# EthIO_03_Ethernet.net
KiCad netlist of a schematic drawn in Altium Designer
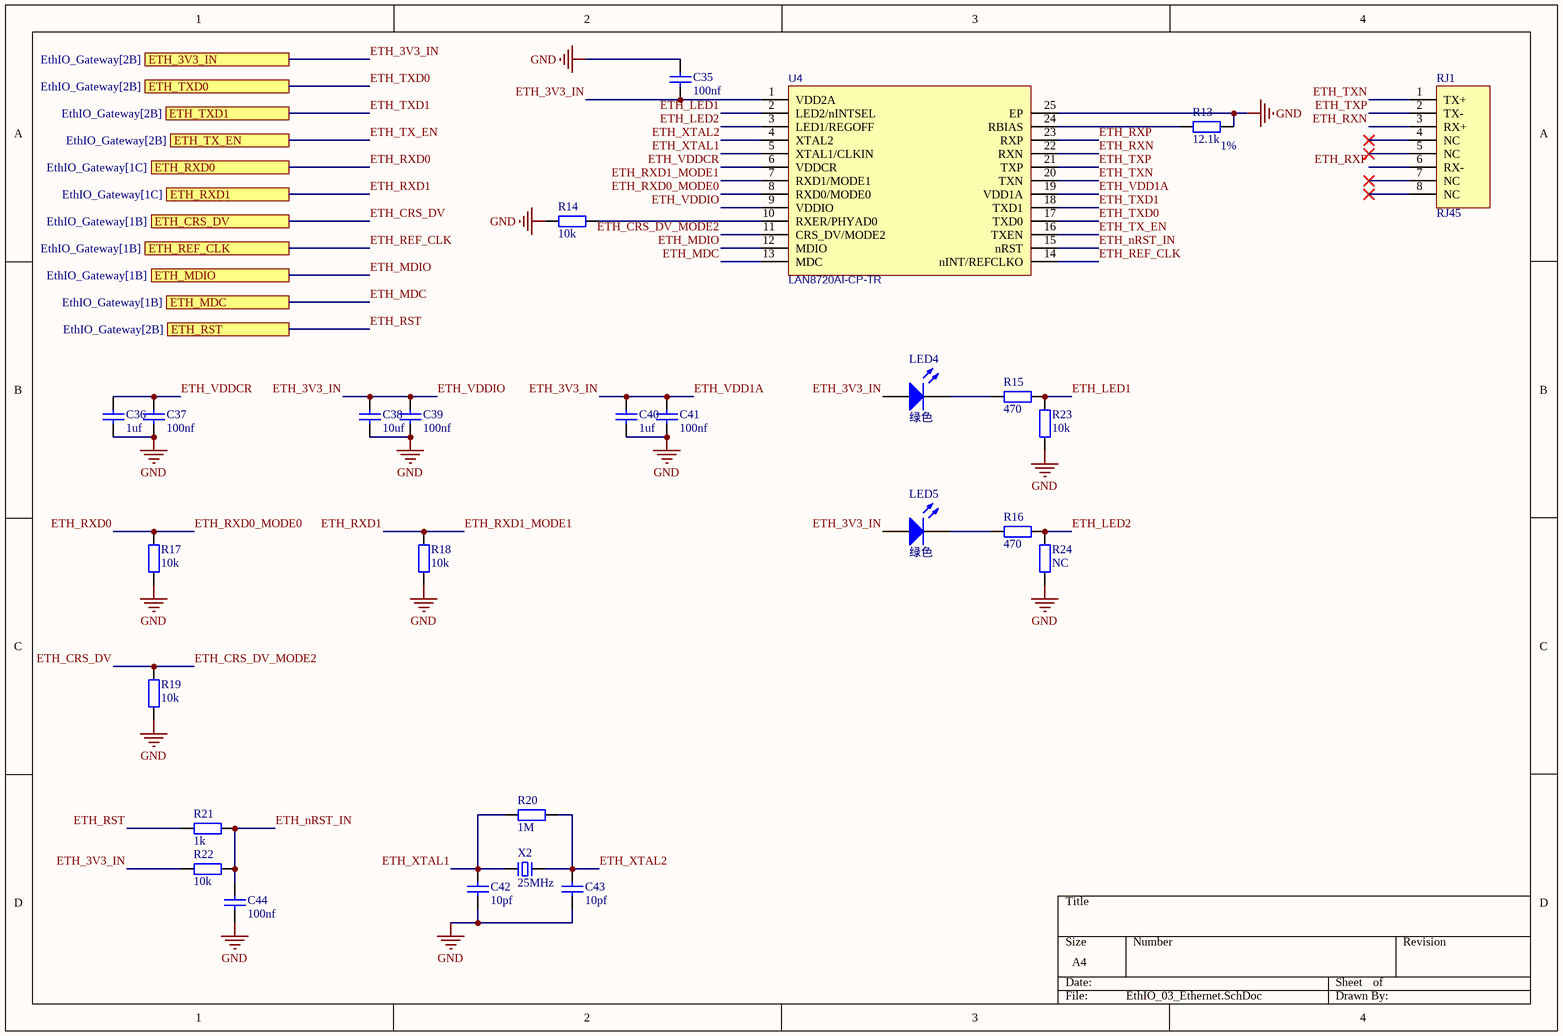
[diagram p0: EthIO_03_Ethernet.SchDoc]

(export (version "E")
  (design (tool "Eeschema 10.0.6"))
  (components
    (comp (ref "C35")
      (value "100nf")
      (footprint "C0805_L")
      (description "贴片电容/MLCC电容")
      (libsource (lib "0.1 - 电阻-电容-电感-保险丝-晶振-晶体-磁珠-电位器-法拉电容-馈通电容") (part "C"))
    )
    (comp (ref "C36")
      (value "1uf")
      (footprint "C0805_L")
      (description "贴片电容/MLCC电容")
      (libsource (lib "0.1 - 电阻-电容-电感-保险丝-晶振-晶体-磁珠-电位器-法拉电容-馈通电容") (part "C"))
    )
    (comp (ref "C37")
      (value "100nf")
      (footprint "C0805_L")
      (description "贴片电容/MLCC电容")
      (libsource (lib "0.1 - 电阻-电容-电感-保险丝-晶振-晶体-磁珠-电位器-法拉电容-馈通电容") (part "C"))
    )
    (comp (ref "C38")
      (value "10uf")
      (footprint "C0805_L")
      (description "贴片电容/MLCC电容")
      (libsource (lib "0.1 - 电阻-电容-电感-保险丝-晶振-晶体-磁珠-电位器-法拉电容-馈通电容") (part "C"))
    )
    (comp (ref "C39")
      (value "100nf")
      (footprint "C0805_L")
      (description "贴片电容/MLCC电容")
      (libsource (lib "0.1 - 电阻-电容-电感-保险丝-晶振-晶体-磁珠-电位器-法拉电容-馈通电容") (part "C"))
    )
    (comp (ref "C40")
      (value "1uf")
      (footprint "C0805_L")
      (description "贴片电容/MLCC电容")
      (libsource (lib "0.1 - 电阻-电容-电感-保险丝-晶振-晶体-磁珠-电位器-法拉电容-馈通电容") (part "C"))
    )
    (comp (ref "C41")
      (value "100nf")
      (footprint "C0805_L")
      (description "贴片电容/MLCC电容")
      (libsource (lib "0.1 - 电阻-电容-电感-保险丝-晶振-晶体-磁珠-电位器-法拉电容-馈通电容") (part "C"))
    )
    (comp (ref "C42")
      (value "10pf")
      (footprint "C0805_L")
      (description "贴片电容/MLCC电容")
      (libsource (lib "0.1 - 电阻-电容-电感-保险丝-晶振-晶体-磁珠-电位器-法拉电容-馈通电容") (part "C"))
    )
    (comp (ref "C43")
      (value "10pf")
      (footprint "C0805_L")
      (description "贴片电容/MLCC电容")
      (libsource (lib "0.1 - 电阻-电容-电感-保险丝-晶振-晶体-磁珠-电位器-法拉电容-馈通电容") (part "C"))
    )
    (comp (ref "C44")
      (value "100nf")
      (footprint "C0805_L")
      (description "贴片电容/MLCC电容")
      (libsource (lib "0.1 - 电阻-电容-电感-保险丝-晶振-晶体-磁珠-电位器-法拉电容-馈通电容") (part "C"))
    )
    (comp (ref "LED4")
      (value "绿色")
      (footprint "LED0805_G")
      (description "贴片LED")
      (libsource (lib "0.3 - LED发光二极管-IR二极管_接收管-光耦") (part "LED"))
    )
    (comp (ref "LED5")
      (value "绿色")
      (footprint "LED0805_G")
      (description "贴片LED")
      (libsource (lib "0.3 - LED发光二极管-IR二极管_接收管-光耦") (part "LED"))
    )
    (comp (ref "R13")
      (value "12.1k")
      (footprint "R0805_L")
      (description "贴片电阻")
      (fields (field (name "TOLERANCE") "1%"))
      (libsource (lib "0.1 - 电阻-电容-电感-保险丝-晶振-晶体-磁珠-电位器-法拉电容-馈通电容") (part "R"))
    )
    (comp (ref "R14")
      (value "10k")
      (footprint "R0805_L")
      (description "贴片电阻")
      (libsource (lib "0.1 - 电阻-电容-电感-保险丝-晶振-晶体-磁珠-电位器-法拉电容-馈通电容") (part "R"))
    )
    (comp (ref "R15")
      (value "470")
      (footprint "R0805_L")
      (description "贴片电阻")
      (libsource (lib "0.1 - 电阻-电容-电感-保险丝-晶振-晶体-磁珠-电位器-法拉电容-馈通电容") (part "R"))
    )
    (comp (ref "R16")
      (value "470")
      (footprint "R0805_L")
      (description "贴片电阻")
      (libsource (lib "0.1 - 电阻-电容-电感-保险丝-晶振-晶体-磁珠-电位器-法拉电容-馈通电容") (part "R"))
    )
    (comp (ref "R17")
      (value "10k")
      (footprint "R0805_L")
      (description "贴片电阻")
      (libsource (lib "0.1 - 电阻-电容-电感-保险丝-晶振-晶体-磁珠-电位器-法拉电容-馈通电容") (part "R"))
    )
    (comp (ref "R18")
      (value "10k")
      (footprint "R0805_L")
      (description "贴片电阻")
      (libsource (lib "0.1 - 电阻-电容-电感-保险丝-晶振-晶体-磁珠-电位器-法拉电容-馈通电容") (part "R"))
    )
    (comp (ref "R19")
      (value "10k")
      (footprint "R0805_L")
      (description "贴片电阻")
      (libsource (lib "0.1 - 电阻-电容-电感-保险丝-晶振-晶体-磁珠-电位器-法拉电容-馈通电容") (part "R"))
    )
    (comp (ref "R20")
      (value "1M")
      (footprint "R0805_L")
      (description "贴片电阻")
      (libsource (lib "0.1 - 电阻-电容-电感-保险丝-晶振-晶体-磁珠-电位器-法拉电容-馈通电容") (part "R"))
    )
    (comp (ref "R21")
      (value "1k")
      (footprint "R0805_L")
      (description "贴片电阻")
      (libsource (lib "0.1 - 电阻-电容-电感-保险丝-晶振-晶体-磁珠-电位器-法拉电容-馈通电容") (part "R"))
    )
    (comp (ref "R22")
      (value "10k")
      (footprint "R0805_L")
      (description "贴片电阻")
      (libsource (lib "0.1 - 电阻-电容-电感-保险丝-晶振-晶体-磁珠-电位器-法拉电容-馈通电容") (part "R"))
    )
    (comp (ref "R23")
      (value "10k")
      (footprint "R0805_L")
      (description "贴片电阻")
      (libsource (lib "0.1 - 电阻-电容-电感-保险丝-晶振-晶体-磁珠-电位器-法拉电容-馈通电容") (part "R"))
    )
    (comp (ref "R24")
      (value "NC")
      (footprint "R0805_L")
      (description "贴片电阻")
      (libsource (lib "0.1 - 电阻-电容-电感-保险丝-晶振-晶体-磁珠-电位器-法拉电容-馈通电容") (part "R"))
    )
    (comp (ref "RJ1")
      (value "RJ45")
      (footprint "RJ45-2")
      (description "以太网接口")
      (libsource (lib "0.6 - 电源_音频_USB Type-C_HDMI_XT60_5557_D-SUB_RJ45_SD-TF_SIM插座") (part "RJ45"))
    )
    (comp (ref "U4")
      (value "LAN8720AI-CP-TR")
      (footprint "QFN24 4x4_N")
      (description "100M 以太网PHY")
      (libsource (lib "0.8 - 常见芯片") (part "LAN8720AI-CP-TR"))
    )
    (comp (ref "X2")
      (value "25MHz")
      (footprint "HC-49S")
      (description "2脚无源晶振(谐振器）")
      (libsource (lib "0.1 - 电阻-电容-电感-保险丝-晶振-晶体-磁珠-电位器-法拉电容-馈通电容") (part "XTAL-2P"))
    )
  )
  (nets
    (net (code "1") (name "/ETH_3V3_IN") (class "Default")
      (node (ref "C35") (pin "2") (pinfunction "2_2") (pintype "passive"))
      (node (ref "C38") (pin "1") (pinfunction "1_1") (pintype "passive"))
      (node (ref "C39") (pin "1") (pinfunction "1_1") (pintype "passive"))
      (node (ref "C40") (pin "1") (pinfunction "1_1") (pintype "passive"))
      (node (ref "C41") (pin "1") (pinfunction "1_1") (pintype "passive"))
      (node (ref "LED4") (pin "1") (pinfunction "A_1") (pintype "passive"))
      (node (ref "LED5") (pin "1") (pinfunction "A_1") (pintype "passive"))
      (node (ref "R22") (pin "1") (pinfunction "1_1") (pintype "passive"))
      (node (ref "U4") (pin "1") (pinfunction "VDD2A_1") (pintype "passive"))
      (node (ref "U4") (pin "19") (pinfunction "VDD1A_19") (pintype "passive"))
      (node (ref "U4") (pin "9") (pinfunction "VDDIO_9") (pintype "passive"))
    )
    (net (code "2") (name "/ETH_CRS_DV") (class "Default")
      (node (ref "R19") (pin "2") (pinfunction "2_2") (pintype "passive"))
      (node (ref "U4") (pin "11") (pinfunction "CRS_DV/MODE2_11") (pintype "passive"))
    )
    (net (code "3") (name "/ETH_LED1") (class "Default")
      (node (ref "R15") (pin "1") (pinfunction "1_1") (pintype "passive"))
      (node (ref "R23") (pin "2") (pinfunction "2_2") (pintype "passive"))
      (node (ref "U4") (pin "2") (pinfunction "LED2/nINTSEL_2") (pintype "passive"))
    )
    (net (code "4") (name "/ETH_LED2") (class "Default")
      (node (ref "R16") (pin "1") (pinfunction "1_1") (pintype "passive"))
      (node (ref "R24") (pin "2") (pinfunction "2_2") (pintype "passive"))
      (node (ref "U4") (pin "3") (pinfunction "LED1/REGOFF_3") (pintype "passive"))
    )
    (net (code "5") (name "/ETH_MDC") (class "Default")
      (node (ref "U4") (pin "13") (pinfunction "MDC_13") (pintype "passive"))
    )
    (net (code "6") (name "/ETH_MDIO") (class "Default")
      (node (ref "U4") (pin "12") (pinfunction "MDIO_12") (pintype "passive"))
    )
    (net (code "7") (name "/ETH_REF_CLK") (class "Default")
      (node (ref "U4") (pin "14") (pinfunction "nINT/REFCLKO_14") (pintype "passive"))
    )
    (net (code "8") (name "/ETH_RST") (class "Default")
      (node (ref "R21") (pin "1") (pinfunction "1_1") (pintype "passive"))
    )
    (net (code "9") (name "/ETH_RXD0") (class "Default")
      (node (ref "R17") (pin "2") (pinfunction "2_2") (pintype "passive"))
      (node (ref "U4") (pin "8") (pinfunction "RXD0/MODE0_8") (pintype "passive"))
    )
    (net (code "10") (name "/ETH_RXD1") (class "Default")
      (node (ref "R18") (pin "2") (pinfunction "2_2") (pintype "passive"))
      (node (ref "U4") (pin "7") (pinfunction "RXD1/MODE1_7") (pintype "passive"))
    )
    (net (code "11") (name "/ETH_RXN") (class "Default")
      (node (ref "RJ1") (pin "3") (pinfunction "RX+_3") (pintype "passive"))
      (node (ref "U4") (pin "22") (pinfunction "RXN_22") (pintype "passive"))
    )
    (net (code "12") (name "/ETH_RXP") (class "Default")
      (node (ref "RJ1") (pin "6") (pinfunction "RX-_6") (pintype "passive"))
      (node (ref "U4") (pin "23") (pinfunction "RXP_23") (pintype "passive"))
    )
    (net (code "13") (name "/ETH_TXD0") (class "Default")
      (node (ref "U4") (pin "17") (pinfunction "TXD0_17") (pintype "passive"))
    )
    (net (code "14") (name "/ETH_TXD1") (class "Default")
      (node (ref "U4") (pin "18") (pinfunction "TXD1_18") (pintype "passive"))
    )
    (net (code "15") (name "/ETH_TXN") (class "Default")
      (node (ref "RJ1") (pin "1") (pinfunction "TX+_1") (pintype "passive"))
      (node (ref "U4") (pin "20") (pinfunction "TXN_20") (pintype "passive"))
    )
    (net (code "16") (name "/ETH_TXP") (class "Default")
      (node (ref "RJ1") (pin "2") (pinfunction "TX-_2") (pintype "passive"))
      (node (ref "U4") (pin "21") (pinfunction "TXP_21") (pintype "passive"))
    )
    (net (code "17") (name "/ETH_TX_EN") (class "Default")
      (node (ref "U4") (pin "16") (pinfunction "TXEN_16") (pintype "passive"))
    )
    (net (code "18") (name "/ETH_VDDCR") (class "Default")
      (node (ref "C36") (pin "1") (pinfunction "1_1") (pintype "passive"))
      (node (ref "C37") (pin "1") (pinfunction "1_1") (pintype "passive"))
      (node (ref "U4") (pin "6") (pinfunction "VDDCR_6") (pintype "passive"))
    )
    (net (code "19") (name "/ETH_XTAL1") (class "Default")
      (node (ref "C42") (pin "1") (pinfunction "1_1") (pintype "passive"))
      (node (ref "R20") (pin "1") (pinfunction "1_1") (pintype "passive"))
      (node (ref "U4") (pin "5") (pinfunction "XTAL1/CLKIN_5") (pintype "passive"))
      (node (ref "X2") (pin "1") (pinfunction "1_1") (pintype "passive"))
    )
    (net (code "20") (name "/ETH_XTAL2") (class "Default")
      (node (ref "C43") (pin "1") (pinfunction "1_1") (pintype "passive"))
      (node (ref "R20") (pin "2") (pinfunction "2_2") (pintype "passive"))
      (node (ref "U4") (pin "4") (pinfunction "XTAL2_4") (pintype "passive"))
      (node (ref "X2") (pin "2") (pinfunction "2_2") (pintype "passive"))
    )
    (net (code "21") (name "/ETH_nRST_IN") (class "Default")
      (node (ref "C44") (pin "1") (pinfunction "1_1") (pintype "passive"))
      (node (ref "R21") (pin "2") (pinfunction "2_2") (pintype "passive"))
      (node (ref "R22") (pin "2") (pinfunction "2_2") (pintype "passive"))
      (node (ref "U4") (pin "15") (pinfunction "nRST_15") (pintype "passive"))
    )
    (net (code "22") (name "GND") (class "Default")
      (node (ref "C35") (pin "1") (pinfunction "1_1") (pintype "passive"))
      (node (ref "C36") (pin "2") (pinfunction "2_2") (pintype "passive"))
      (node (ref "C37") (pin "2") (pinfunction "2_2") (pintype "passive"))
      (node (ref "C38") (pin "2") (pinfunction "2_2") (pintype "passive"))
      (node (ref "C39") (pin "2") (pinfunction "2_2") (pintype "passive"))
      (node (ref "C40") (pin "2") (pinfunction "2_2") (pintype "passive"))
      (node (ref "C41") (pin "2") (pinfunction "2_2") (pintype "passive"))
      (node (ref "C42") (pin "2") (pinfunction "2_2") (pintype "passive"))
      (node (ref "C43") (pin "2") (pinfunction "2_2") (pintype "passive"))
      (node (ref "C44") (pin "2") (pinfunction "2_2") (pintype "passive"))
      (node (ref "R13") (pin "1") (pinfunction "1_1") (pintype "passive"))
      (node (ref "R14") (pin "2") (pinfunction "2_2") (pintype "passive"))
      (node (ref "R17") (pin "1") (pinfunction "1_1") (pintype "passive"))
      (node (ref "R18") (pin "1") (pinfunction "1_1") (pintype "passive"))
      (node (ref "R19") (pin "1") (pinfunction "1_1") (pintype "passive"))
      (node (ref "R23") (pin "1") (pinfunction "1_1") (pintype "passive"))
      (node (ref "R24") (pin "1") (pinfunction "1_1") (pintype "passive"))
      (node (ref "U4") (pin "25") (pinfunction "EP_25") (pintype "passive"))
    )
    (net (code "23") (name "Net-(LED4-K)") (class "Default")
      (node (ref "LED4") (pin "2") (pinfunction "K_2") (pintype "passive"))
      (node (ref "R15") (pin "2") (pinfunction "2_2") (pintype "passive"))
    )
    (net (code "24") (name "Net-(LED5-K)") (class "Default")
      (node (ref "LED5") (pin "2") (pinfunction "K_2") (pintype "passive"))
      (node (ref "R16") (pin "2") (pinfunction "2_2") (pintype "passive"))
    )
    (net (code "25") (name "Net-(U4-RBIAS)") (class "Default")
      (node (ref "R13") (pin "2") (pinfunction "2_2") (pintype "passive"))
      (node (ref "U4") (pin "24") (pinfunction "RBIAS_24") (pintype "passive"))
    )
    (net (code "26") (name "Net-(U4-RXER{slash}PHYAD0)") (class "Default")
      (node (ref "R14") (pin "1") (pinfunction "1_1") (pintype "passive"))
      (node (ref "U4") (pin "10") (pinfunction "RXER/PHYAD0_10") (pintype "passive"))
    )
    (net (code "27") (name "unconnected-(RJ1-NC-Pad4)") (class "Default")
      (node (ref "RJ1") (pin "4") (pinfunction "NC_4") (pintype "passive+no_connect"))
    )
    (net (code "28") (name "unconnected-(RJ1-NC-Pad5)") (class "Default")
      (node (ref "RJ1") (pin "5") (pinfunction "NC_5") (pintype "passive+no_connect"))
    )
    (net (code "29") (name "unconnected-(RJ1-NC-Pad7)") (class "Default")
      (node (ref "RJ1") (pin "7") (pinfunction "NC_7") (pintype "passive+no_connect"))
    )
    (net (code "30") (name "unconnected-(RJ1-NC-Pad8)") (class "Default")
      (node (ref "RJ1") (pin "8") (pinfunction "NC_8") (pintype "passive+no_connect"))
    )
  )
)
